# LEDS_Demo.net
KiCad netlist of a schematic drawn in Altium Designer
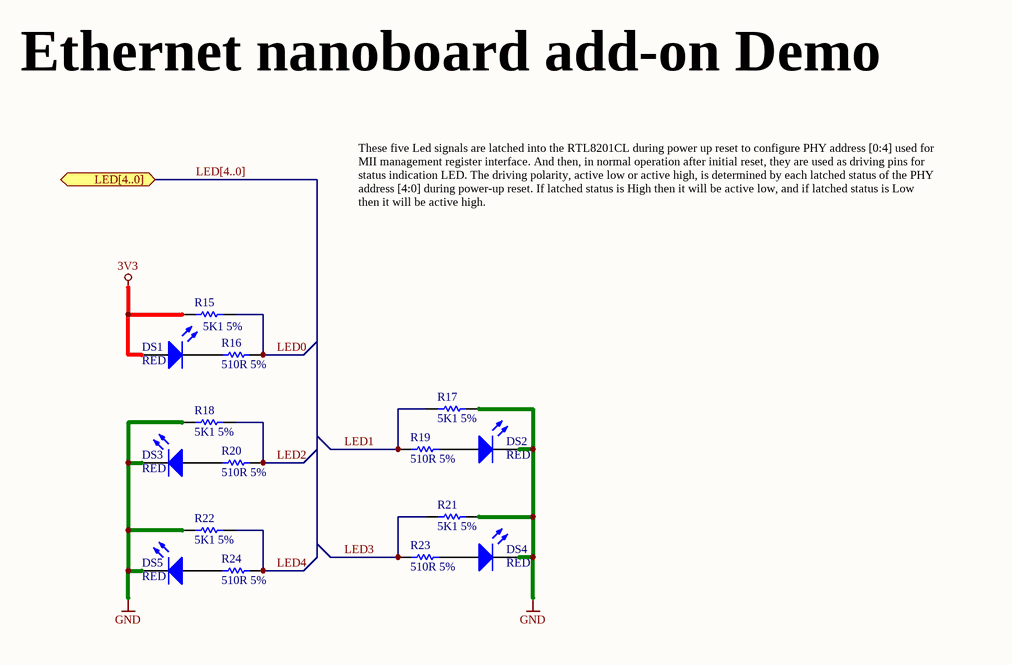
[diagram p0: LEDS_Demo.SchDoc]

(export (version "E")
  (design (tool "Eeschema 10.0.6"))
  (components
    (comp (ref "DS1")
      (value "RED")
      (footprint "PHY_Demo:LED2013")
      (description "Typical GREEN SMD LED Agilent make")
      (libsource (lib "Altium Design Library") (part "DIO-LED-1S"))
    )
    (comp (ref "DS2")
      (value "RED")
      (footprint "PHY_Demo:LED2013")
      (description "Typical GREEN SMD LED Agilent make")
      (libsource (lib "Altium Design Library") (part "DIO-LED-1S"))
    )
    (comp (ref "DS3")
      (value "RED")
      (footprint "PHY_Demo:LED2013")
      (description "Typical GREEN SMD LED Agilent make")
      (libsource (lib "Altium Design Library") (part "DIO-LED-1S"))
    )
    (comp (ref "DS4")
      (value "RED")
      (footprint "PHY_Demo:LED2013")
      (description "Typical GREEN SMD LED Agilent make")
      (libsource (lib "Altium Design Library") (part "DIO-LED-1S"))
    )
    (comp (ref "DS5")
      (value "RED")
      (footprint "PHY_Demo:LED2013")
      (description "Typical GREEN SMD LED Agilent make")
      (libsource (lib "Altium Design Library") (part "DIO-LED-1S"))
    )
    (comp (ref "R15")
      (value "5K1 5%")
      (footprint "PHY_Demo:RESC2012")
      (description "Resistor")
      (libsource (lib "Altium Design Library") (part "RES"))
    )
    (comp (ref "R16")
      (value "510R 5%")
      (footprint "PHY_Demo:RESC2012")
      (description "Resistor")
      (libsource (lib "Altium Design Library") (part "RES"))
    )
    (comp (ref "R17")
      (value "5K1 5%")
      (footprint "PHY_Demo:RESC2012")
      (description "Resistor")
      (libsource (lib "Altium Design Library") (part "RES"))
    )
    (comp (ref "R18")
      (value "5K1 5%")
      (footprint "PHY_Demo:RESC2012")
      (description "Resistor")
      (libsource (lib "Altium Design Library") (part "RES"))
    )
    (comp (ref "R19")
      (value "510R 5%")
      (footprint "PHY_Demo:RESC2012")
      (description "Resistor")
      (libsource (lib "Altium Design Library") (part "RES"))
    )
    (comp (ref "R20")
      (value "510R 5%")
      (footprint "PHY_Demo:RESC2012")
      (description "Resistor")
      (libsource (lib "Altium Design Library") (part "RES"))
    )
    (comp (ref "R21")
      (value "5K1 5%")
      (footprint "PHY_Demo:RESC2012")
      (description "Resistor")
      (libsource (lib "Altium Design Library") (part "RES"))
    )
    (comp (ref "R22")
      (value "5K1 5%")
      (footprint "PHY_Demo:RESC2012")
      (description "Resistor")
      (libsource (lib "Altium Design Library") (part "RES"))
    )
    (comp (ref "R23")
      (value "510R 5%")
      (footprint "PHY_Demo:RESC2012")
      (description "Resistor")
      (libsource (lib "Altium Design Library") (part "RES"))
    )
    (comp (ref "R24")
      (value "510R 5%")
      (footprint "PHY_Demo:RESC2012")
      (description "Resistor")
      (libsource (lib "Altium Design Library") (part "RES"))
    )
  )
  (nets
    (net (code "1") (name "/LED0") (class "Default")
      (node (ref "R15") (pin "1") (pinfunction "1_1") (pintype "passive"))
      (node (ref "R16") (pin "1") (pinfunction "1_1") (pintype "passive"))
    )
    (net (code "2") (name "/LED1") (class "Default")
      (node (ref "R17") (pin "2") (pinfunction "2_2") (pintype "passive"))
      (node (ref "R19") (pin "1") (pinfunction "1_1") (pintype "passive"))
    )
    (net (code "3") (name "/LED2") (class "Default")
      (node (ref "R18") (pin "1") (pinfunction "1_1") (pintype "passive"))
      (node (ref "R20") (pin "1") (pinfunction "1_1") (pintype "passive"))
    )
    (net (code "4") (name "/LED3") (class "Default")
      (node (ref "R21") (pin "2") (pinfunction "2_2") (pintype "passive"))
      (node (ref "R23") (pin "1") (pinfunction "1_1") (pintype "passive"))
    )
    (net (code "5") (name "/LED4") (class "Default")
      (node (ref "R22") (pin "1") (pinfunction "1_1") (pintype "passive"))
      (node (ref "R24") (pin "1") (pinfunction "1_1") (pintype "passive"))
    )
    (net (code "7") (name "3V3") (class "Default")
      (node (ref "DS1") (pin "1") (pinfunction "A_1") (pintype "passive"))
      (node (ref "R15") (pin "2") (pinfunction "2_2") (pintype "passive"))
    )
    (net (code "8") (name "GND") (class "Default")
      (node (ref "DS2") (pin "2") (pinfunction "K_2") (pintype "passive"))
      (node (ref "DS3") (pin "2") (pinfunction "K_2") (pintype "passive"))
      (node (ref "DS4") (pin "2") (pinfunction "K_2") (pintype "passive"))
      (node (ref "DS5") (pin "2") (pinfunction "K_2") (pintype "passive"))
      (node (ref "R17") (pin "1") (pinfunction "1_1") (pintype "passive"))
      (node (ref "R18") (pin "2") (pinfunction "2_2") (pintype "passive"))
      (node (ref "R21") (pin "1") (pinfunction "1_1") (pintype "passive"))
      (node (ref "R22") (pin "2") (pinfunction "2_2") (pintype "passive"))
    )
    (net (code "9") (name "Net-(DS1-K)") (class "Default")
      (node (ref "DS1") (pin "2") (pinfunction "K_2") (pintype "passive"))
      (node (ref "R16") (pin "2") (pinfunction "2_2") (pintype "passive"))
    )
    (net (code "10") (name "Net-(DS2-A)") (class "Default")
      (node (ref "DS2") (pin "1") (pinfunction "A_1") (pintype "passive"))
      (node (ref "R19") (pin "2") (pinfunction "2_2") (pintype "passive"))
    )
    (net (code "11") (name "Net-(DS3-A)") (class "Default")
      (node (ref "DS3") (pin "1") (pinfunction "A_1") (pintype "passive"))
      (node (ref "R20") (pin "2") (pinfunction "2_2") (pintype "passive"))
    )
    (net (code "12") (name "Net-(DS4-A)") (class "Default")
      (node (ref "DS4") (pin "1") (pinfunction "A_1") (pintype "passive"))
      (node (ref "R23") (pin "2") (pinfunction "2_2") (pintype "passive"))
    )
    (net (code "13") (name "Net-(DS5-A)") (class "Default")
      (node (ref "DS5") (pin "1") (pinfunction "A_1") (pintype "passive"))
      (node (ref "R24") (pin "2") (pinfunction "2_2") (pintype "passive"))
    )
  )
)
